# MyFly1.net
KiCad netlist of a schematic drawn in Altium Designer
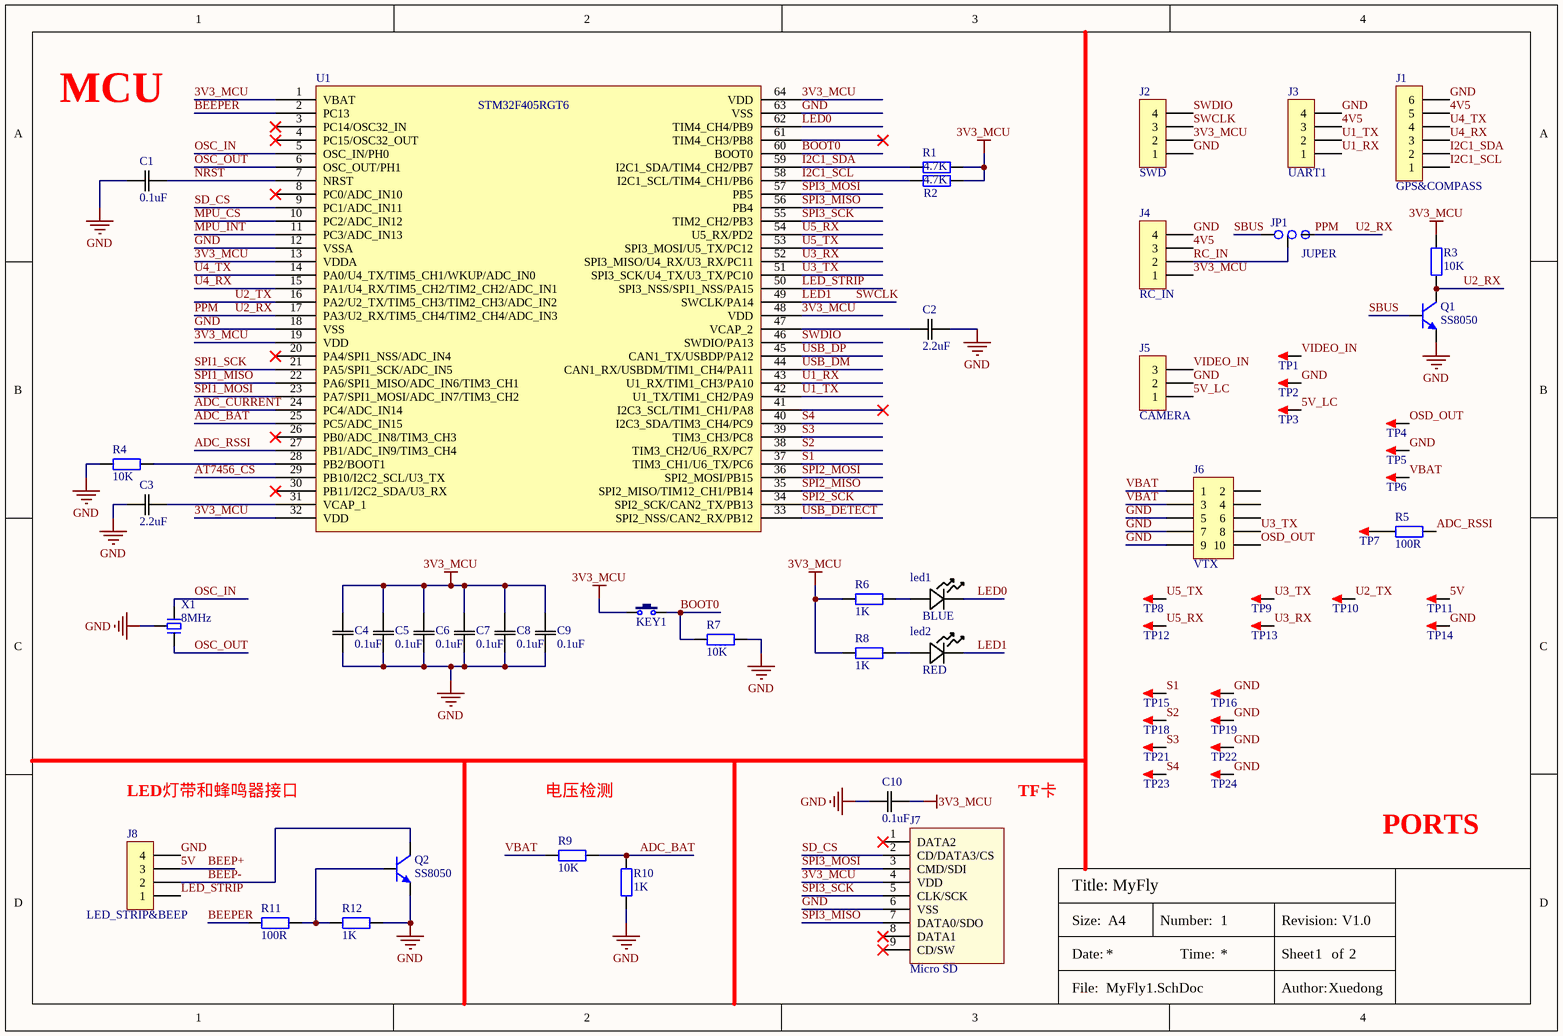
[diagram p0: MyFly1.SchDoc]

(export (version "E")
  (design (tool "Eeschema 10.0.6"))
  (components
    (comp (ref "C1")
      (value "0.1uF")
      (footprint "CAP_0402")
      (description "无极性贴片电容")
      (fields
        (field (name "MANUFACTURER_PART_NUMBER") "04023A0R3BAT2A")
        (field (name "COPYRIGHT") "Copyright (C) 2016 Accelerated Designs. All rights reserved")
      )
      (libsource (lib "mySchLib") (part "CAP"))
    )
    (comp (ref "C2")
      (value "2.2uF")
      (footprint "CAP_0402")
      (description "无极性贴片电容")
      (fields
        (field (name "MANUFACTURER_PART_NUMBER") "04023A0R3BAT2A")
        (field (name "COPYRIGHT") "Copyright (C) 2016 Accelerated Designs. All rights reserved")
      )
      (libsource (lib "mySchLib") (part "CAP"))
    )
    (comp (ref "C3")
      (value "2.2uF")
      (footprint "CAP_0402")
      (description "无极性贴片电容")
      (fields
        (field (name "MANUFACTURER_PART_NUMBER") "04023A0R3BAT2A")
        (field (name "COPYRIGHT") "Copyright (C) 2016 Accelerated Designs. All rights reserved")
      )
      (libsource (lib "mySchLib") (part "CAP"))
    )
    (comp (ref "C4")
      (value "0.1uF")
      (footprint "CAP_0402")
      (description "无极性贴片电容")
      (fields
        (field (name "MANUFACTURER_PART_NUMBER") "04023A0R3BAT2A")
        (field (name "COPYRIGHT") "Copyright (C) 2016 Accelerated Designs. All rights reserved")
      )
      (libsource (lib "mySchLib") (part "CAP"))
    )
    (comp (ref "C5")
      (value "0.1uF")
      (footprint "CAP_0402")
      (description "无极性贴片电容")
      (fields
        (field (name "MANUFACTURER_PART_NUMBER") "04023A0R3BAT2A")
        (field (name "COPYRIGHT") "Copyright (C) 2016 Accelerated Designs. All rights reserved")
      )
      (libsource (lib "mySchLib") (part "CAP"))
    )
    (comp (ref "C6")
      (value "0.1uF")
      (footprint "CAP_0402")
      (description "无极性贴片电容")
      (fields
        (field (name "MANUFACTURER_PART_NUMBER") "04023A0R3BAT2A")
        (field (name "COPYRIGHT") "Copyright (C) 2016 Accelerated Designs. All rights reserved")
      )
      (libsource (lib "mySchLib") (part "CAP"))
    )
    (comp (ref "C7")
      (value "0.1uF")
      (footprint "CAP_0402")
      (description "无极性贴片电容")
      (fields
        (field (name "MANUFACTURER_PART_NUMBER") "04023A0R3BAT2A")
        (field (name "COPYRIGHT") "Copyright (C) 2016 Accelerated Designs. All rights reserved")
      )
      (libsource (lib "mySchLib") (part "CAP"))
    )
    (comp (ref "C8")
      (value "0.1uF")
      (footprint "CAP_0402")
      (description "无极性贴片电容")
      (fields
        (field (name "MANUFACTURER_PART_NUMBER") "04023A0R3BAT2A")
        (field (name "COPYRIGHT") "Copyright (C) 2016 Accelerated Designs. All rights reserved")
      )
      (libsource (lib "mySchLib") (part "CAP"))
    )
    (comp (ref "C9")
      (value "0.1uF")
      (footprint "CAP_0402")
      (description "无极性贴片电容")
      (fields
        (field (name "MANUFACTURER_PART_NUMBER") "04023A0R3BAT2A")
        (field (name "COPYRIGHT") "Copyright (C) 2016 Accelerated Designs. All rights reserved")
      )
      (libsource (lib "mySchLib") (part "CAP"))
    )
    (comp (ref "C10")
      (value "0.1uF")
      (footprint "CAP_0603")
      (description "无极性贴片电容")
      (fields
        (field (name "MANUFACTURER_PART_NUMBER") "04023A0R3BAT2A")
        (field (name "COPYRIGHT") "Copyright (C) 2016 Accelerated Designs. All rights reserved")
      )
      (libsource (lib "mySchLib") (part "CAP"))
    )
    (comp (ref "J1")
      (value "GPS&COMPASS")
      (footprint "SH1.0 S-W-6P")
      (description "6P接插件")
      (fields (field (name "MANUFACTURER_PART_NUMBER") "826629-6"))
      (libsource (lib "mySchLib") (part "Header_1x6"))
    )
    (comp (ref "J2")
      (value "SWD")
      (footprint "SH1.0 S-W-4P")
      (description "4P接插件")
      (fields (field (name "MANUFACTURER_PART_NUMBER") "826629-4"))
      (libsource (lib "mySchLib") (part "Header_1x4"))
    )
    (comp (ref "J3")
      (value "UART1")
      (footprint "SH1.0 S-W-4P")
      (description "4P接插件")
      (fields (field (name "MANUFACTURER_PART_NUMBER") "826629-4"))
      (libsource (lib "mySchLib") (part "Header_1x4"))
    )
    (comp (ref "J4")
      (value "RC_IN")
      (footprint "SH1.0 S-W-4P")
      (description "4P接插件")
      (fields (field (name "MANUFACTURER_PART_NUMBER") "826629-4"))
      (libsource (lib "mySchLib") (part "Header_1x4"))
    )
    (comp (ref "J5")
      (value "CAMERA")
      (footprint "MX 1.25-WS-3P")
      (description "3P接插件")
      (fields (field (name "MANUFACTURER_PART_NUMBER") "826629-3"))
      (libsource (lib "mySchLib") (part "Header_1x3"))
    )
    (comp (ref "J6")
      (value "VTX")
      (footprint "HDR1.27 2x5-M-SMD")
      (description "2x5P-接插件")
      (fields (field (name "MANUFACTURER_PART_NUMBER") "826656-5"))
      (libsource (lib "mySchLib") (part "Header_2x5"))
    )
    (comp (ref "J7")
      (value "Micro SD")
      (footprint "MICRO SD")
      (description "Micro SD卡")
      (fields (field (name "版权归属") "源创客"))
      (libsource (lib "mySchLib") (part "Micro SD"))
    )
    (comp (ref "J8")
      (value "LED_STRIP&BEEP")
      (footprint "SH1.0 S-W-4P")
      (description "4P接插件")
      (fields (field (name "MANUFACTURER_PART_NUMBER") "826629-4"))
      (libsource (lib "mySchLib") (part "Header_1x4"))
    )
    (comp (ref "JP1")
      (value "JUPER")
      (footprint "JUMPER 3P")
      (description "三点焊盘跳线")
      (libsource (lib "mySchLib") (part "JUMPER 3P"))
    )
    (comp (ref "KEY1")
      (value "KEY")
      (footprint "KEY_TSW 2*4*3.5-S-W")
      (description "按键")
      (fields (field (name "版权归属") "源创客"))
      (libsource (lib "mySchLib") (part "KEY"))
    )
    (comp (ref "led1")
      (value "BLUE")
      (footprint "LED_0603")
      (description "贴片发光二极管")
      (fields (field (name "MANUFACTURER_PART_NUMBER") "VLMB1310-GS08"))
      (libsource (lib "mySchLib") (part "LED"))
    )
    (comp (ref "led2")
      (value "RED")
      (footprint "LED_0603")
      (description "贴片发光二极管")
      (fields (field (name "MANUFACTURER_PART_NUMBER") "VLMB1310-GS08"))
      (libsource (lib "mySchLib") (part "LED"))
    )
    (comp (ref "Q1")
      (value "SS8050")
      (footprint "SOT23-3L")
      (description "高频放大-NPN型")
      (fields (field (name "版权归属") "源创客"))
      (libsource (lib "mySchLib") (part "S8050-SMD"))
    )
    (comp (ref "Q2")
      (value "SS8050")
      (footprint "SOT23-3L")
      (description "高频放大-NPN型")
      (fields (field (name "版权归属") "源创客"))
      (libsource (lib "mySchLib") (part "S8050-SMD"))
    )
    (comp (ref "R1")
      (value "4.7K")
      (footprint "Res_0402")
      (description "贴片电阻")
      (fields (field (name "MANUFACTURER_PART_NUMBER") "RC0402FR-070RL"))
      (libsource (lib "mySchLib") (part "RES"))
    )
    (comp (ref "R2")
      (value "4.7K")
      (footprint "Res_0402")
      (description "贴片电阻")
      (fields (field (name "MANUFACTURER_PART_NUMBER") "RC0402FR-070RL"))
      (libsource (lib "mySchLib") (part "RES"))
    )
    (comp (ref "R3")
      (value "10K")
      (footprint "Res_0402")
      (description "贴片电阻")
      (fields (field (name "MANUFACTURER_PART_NUMBER") "RC0402FR-070RL"))
      (libsource (lib "mySchLib") (part "RES"))
    )
    (comp (ref "R4")
      (value "10K")
      (footprint "Res_0402")
      (description "贴片电阻")
      (fields (field (name "MANUFACTURER_PART_NUMBER") "RC0402FR-070RL"))
      (libsource (lib "mySchLib") (part "RES"))
    )
    (comp (ref "R5")
      (value "100R")
      (footprint "Res_0402")
      (description "贴片电阻")
      (fields (field (name "MANUFACTURER_PART_NUMBER") "RC0402FR-070RL"))
      (libsource (lib "mySchLib") (part "RES"))
    )
    (comp (ref "R6")
      (value "1K")
      (footprint "Res_0402")
      (description "贴片电阻")
      (fields (field (name "MANUFACTURER_PART_NUMBER") "RC0402FR-070RL"))
      (libsource (lib "mySchLib") (part "RES"))
    )
    (comp (ref "R7")
      (value "10K")
      (footprint "Res_0402")
      (description "贴片电阻")
      (fields (field (name "MANUFACTURER_PART_NUMBER") "RC0402FR-070RL"))
      (libsource (lib "mySchLib") (part "RES"))
    )
    (comp (ref "R8")
      (value "1K")
      (footprint "Res_0402")
      (description "贴片电阻")
      (fields (field (name "MANUFACTURER_PART_NUMBER") "RC0402FR-070RL"))
      (libsource (lib "mySchLib") (part "RES"))
    )
    (comp (ref "R9")
      (value "10K")
      (footprint "RES_0603")
      (description "贴片电阻")
      (fields (field (name "MANUFACTURER_PART_NUMBER") "RC0402FR-070RL"))
      (libsource (lib "mySchLib") (part "RES"))
    )
    (comp (ref "R10")
      (value "1K")
      (footprint "RES_0603")
      (description "贴片电阻")
      (fields (field (name "MANUFACTURER_PART_NUMBER") "RC0402FR-070RL"))
      (libsource (lib "mySchLib") (part "RES"))
    )
    (comp (ref "R11")
      (value "100R")
      (footprint "Res_0402")
      (description "贴片电阻")
      (fields (field (name "MANUFACTURER_PART_NUMBER") "RC0402FR-070RL"))
      (libsource (lib "mySchLib") (part "RES"))
    )
    (comp (ref "R12")
      (value "1K")
      (footprint "Res_0402")
      (description "贴片电阻")
      (fields (field (name "MANUFACTURER_PART_NUMBER") "RC0402FR-070RL"))
      (libsource (lib "mySchLib") (part "RES"))
    )
    (comp (ref "TP1")
      (value "TEST")
      (footprint "TEST PAD 1.8")
      (description "测试点")
      (fields (field (name "版权归属") "源创客"))
      (libsource (lib "mySchLib") (part "TEST"))
    )
    (comp (ref "TP2")
      (value "TEST")
      (footprint "TEST PAD 1.8")
      (description "测试点")
      (fields (field (name "版权归属") "源创客"))
      (libsource (lib "mySchLib") (part "TEST"))
    )
    (comp (ref "TP3")
      (value "TEST")
      (footprint "TEST PAD 1.8")
      (description "测试点")
      (fields (field (name "版权归属") "源创客"))
      (libsource (lib "mySchLib") (part "TEST"))
    )
    (comp (ref "TP4")
      (value "TEST")
      (footprint "TEST PAD 1.8")
      (description "测试点")
      (fields (field (name "版权归属") "源创客"))
      (libsource (lib "mySchLib") (part "TEST"))
    )
    (comp (ref "TP5")
      (value "TEST")
      (footprint "TEST PAD 1.8")
      (description "测试点")
      (fields (field (name "版权归属") "源创客"))
      (libsource (lib "mySchLib") (part "TEST"))
    )
    (comp (ref "TP6")
      (value "TEST")
      (footprint "TEST PAD 1.8")
      (description "测试点")
      (fields (field (name "版权归属") "源创客"))
      (libsource (lib "mySchLib") (part "TEST"))
    )
    (comp (ref "TP7")
      (value "TEST")
      (footprint "TEST PAD 1.8")
      (description "测试点")
      (fields (field (name "版权归属") "源创客"))
      (libsource (lib "mySchLib") (part "TEST"))
    )
    (comp (ref "TP8")
      (value "TEST")
      (footprint "TEST PAD 1.8")
      (description "测试点")
      (fields (field (name "版权归属") "源创客"))
      (libsource (lib "mySchLib") (part "TEST"))
    )
    (comp (ref "TP9")
      (value "TEST")
      (footprint "TEST PAD 1.8")
      (description "测试点")
      (fields (field (name "版权归属") "源创客"))
      (libsource (lib "mySchLib") (part "TEST"))
    )
    (comp (ref "TP10")
      (value "TEST")
      (footprint "TEST PAD 1.8")
      (description "测试点")
      (fields (field (name "版权归属") "源创客"))
      (libsource (lib "mySchLib") (part "TEST"))
    )
    (comp (ref "TP11")
      (value "TEST")
      (footprint "TEST PAD 1.8")
      (description "测试点")
      (fields (field (name "版权归属") "源创客"))
      (libsource (lib "mySchLib") (part "TEST"))
    )
    (comp (ref "TP12")
      (value "TEST")
      (footprint "TEST PAD 1.8")
      (description "测试点")
      (fields (field (name "版权归属") "源创客"))
      (libsource (lib "mySchLib") (part "TEST"))
    )
    (comp (ref "TP13")
      (value "TEST")
      (footprint "TEST PAD 1.8")
      (description "测试点")
      (fields (field (name "版权归属") "源创客"))
      (libsource (lib "mySchLib") (part "TEST"))
    )
    (comp (ref "TP14")
      (value "TEST")
      (footprint "TEST PAD 1.8")
      (description "测试点")
      (fields (field (name "版权归属") "源创客"))
      (libsource (lib "mySchLib") (part "TEST"))
    )
    (comp (ref "TP15")
      (value "TEST")
      (footprint "TEST PAD 1.8")
      (description "测试点")
      (fields (field (name "版权归属") "源创客"))
      (libsource (lib "mySchLib") (part "TEST"))
    )
    (comp (ref "TP16")
      (value "TEST")
      (footprint "TEST PAD 1.8")
      (description "测试点")
      (fields (field (name "版权归属") "源创客"))
      (libsource (lib "mySchLib") (part "TEST"))
    )
    (comp (ref "TP18")
      (value "TEST")
      (footprint "TEST PAD 1.8")
      (description "测试点")
      (fields (field (name "版权归属") "源创客"))
      (libsource (lib "mySchLib") (part "TEST"))
    )
    (comp (ref "TP19")
      (value "TEST")
      (footprint "TEST PAD 1.8")
      (description "测试点")
      (fields (field (name "版权归属") "源创客"))
      (libsource (lib "mySchLib") (part "TEST"))
    )
    (comp (ref "TP21")
      (value "TEST")
      (footprint "TEST PAD 1.8")
      (description "测试点")
      (fields (field (name "版权归属") "源创客"))
      (libsource (lib "mySchLib") (part "TEST"))
    )
    (comp (ref "TP22")
      (value "TEST")
      (footprint "TEST PAD 1.8")
      (description "测试点")
      (fields (field (name "版权归属") "源创客"))
      (libsource (lib "mySchLib") (part "TEST"))
    )
    (comp (ref "TP23")
      (value "TEST")
      (footprint "TEST PAD 1.8")
      (description "测试点")
      (fields (field (name "版权归属") "源创客"))
      (libsource (lib "mySchLib") (part "TEST"))
    )
    (comp (ref "TP24")
      (value "TEST")
      (footprint "TEST PAD 1.8")
      (description "测试点")
      (fields (field (name "版权归属") "源创客"))
      (libsource (lib "mySchLib") (part "TEST"))
    )
    (comp (ref "U1")
      (value "STM32F405RGT6")
      (footprint "LQFP-64")
      (description "Flaah:256/RAM:48/IO:51")
      (libsource (lib "mySchLib") (part "STM32F405RGT6"))
    )
    (comp (ref "X1")
      (value "8MHz")
      (footprint "XTAL-3215-3P")
      (description "3脚无源晶振")
      (fields (field (name "版权归属") "源创客"))
      (libsource (lib "mySchLib") (part "XTAL-3P"))
    )
  )
  (nets
    (net (code "1") (name "/4V5") (class "Default")
      (node (ref "J1") (pin "5") (pinfunction "5_5") (pintype "passive"))
      (node (ref "J3") (pin "3") (pinfunction "3_3") (pintype "passive"))
      (node (ref "J4") (pin "3") (pinfunction "3_3") (pintype "passive"))
    )
    (net (code "2") (name "/5V") (class "Default")
      (node (ref "J8") (pin "3") (pinfunction "3_3") (pintype "passive"))
      (node (ref "TP11") (pin "1") (pinfunction "1_1") (pintype "passive"))
    )
    (net (code "3") (name "/5V_LC") (class "Default")
      (node (ref "J5") (pin "1") (pinfunction "1_1") (pintype "passive"))
      (node (ref "TP3") (pin "1") (pinfunction "1_1") (pintype "passive"))
    )
    (net (code "4") (name "/ADC_BAT") (class "Default")
      (node (ref "R10") (pin "2") (pinfunction "2_2") (pintype "passive"))
      (node (ref "R9") (pin "2") (pinfunction "2_2") (pintype "passive"))
      (node (ref "U1") (pin "25") (pinfunction "PC5/ADC_IN15_25") (pintype "passive"))
    )
    (net (code "5") (name "/ADC_CURRENT") (class "Default")
      (node (ref "U1") (pin "24") (pinfunction "PC4/ADC_IN14_24") (pintype "passive"))
    )
    (net (code "6") (name "/ADC_RSSI") (class "Default")
      (node (ref "R5") (pin "2") (pinfunction "2_2") (pintype "passive"))
      (node (ref "U1") (pin "27") (pinfunction "PB1/ADC_IN9/TIM3_CH4_27") (pintype "passive"))
    )
    (net (code "7") (name "/AT7456_CS") (class "Default")
      (node (ref "U1") (pin "29") (pinfunction "PB10/I2C2_SCL/U3_TX_29") (pintype "passive"))
    )
    (net (code "8") (name "/BEEP-") (class "Default")
      (node (ref "J8") (pin "2") (pinfunction "2_2") (pintype "passive"))
      (node (ref "Q2") (pin "3") (pinfunction "C_3") (pintype "passive"))
    )
    (net (code "9") (name "/BEEPER") (class "Default")
      (node (ref "R11") (pin "1") (pinfunction "1_1") (pintype "passive"))
      (node (ref "U1") (pin "2") (pinfunction "PC13_2") (pintype "passive"))
    )
    (net (code "10") (name "/BOOT0") (class "Default")
      (node (ref "KEY1") (pin "2") (pinfunction "2_2") (pintype "passive"))
      (node (ref "R7") (pin "1") (pinfunction "1_1") (pintype "passive"))
      (node (ref "U1") (pin "60") (pinfunction "BOOT0_60") (pintype "passive"))
    )
    (net (code "11") (name "/I2C1_SCL") (class "Default")
      (node (ref "J1") (pin "1") (pinfunction "1_1") (pintype "passive"))
      (node (ref "R2") (pin "1") (pinfunction "1_1") (pintype "passive"))
      (node (ref "U1") (pin "58") (pinfunction "I2C1_SCL/TIM4_CH1/PB6_58") (pintype "passive"))
    )
    (net (code "12") (name "/I2C1_SDA") (class "Default")
      (node (ref "J1") (pin "2") (pinfunction "2_2") (pintype "passive"))
      (node (ref "R1") (pin "1") (pinfunction "1_1") (pintype "passive"))
      (node (ref "U1") (pin "59") (pinfunction "I2C1_SDA/TIM4_CH2/PB7_59") (pintype "passive"))
    )
    (net (code "13") (name "/LED0") (class "Default")
      (node (ref "U1") (pin "62") (pinfunction "TIM4_CH4/PB9_62") (pintype "passive"))
      (node (ref "led1") (pin "1") (pinfunction "1_1") (pintype "passive"))
    )
    (net (code "14") (name "/LED1") (class "Default")
      (node (ref "J2") (pin "3") (pinfunction "3_3") (pintype "passive"))
      (node (ref "U1") (pin "49") (pinfunction "SWCLK/PA14_49") (pintype "passive"))
      (node (ref "led2") (pin "1") (pinfunction "1_1") (pintype "passive"))
    )
    (net (code "15") (name "/LED_STRIP") (class "Default")
      (node (ref "J8") (pin "1") (pinfunction "1_1") (pintype "passive"))
      (node (ref "U1") (pin "50") (pinfunction "SPI3_NSS/SPI1_NSS/PA15_50") (pintype "passive"))
    )
    (net (code "16") (name "/MPU_CS") (class "Default")
      (node (ref "U1") (pin "10") (pinfunction "PC2/ADC_IN12_10") (pintype "passive"))
    )
    (net (code "17") (name "/MPU_INT") (class "Default")
      (node (ref "U1") (pin "11") (pinfunction "PC3/ADC_IN13_11") (pintype "passive"))
    )
    (net (code "18") (name "/NRST") (class "Default")
      (node (ref "C1") (pin "2") (pinfunction "EPAD_2") (pintype "passive"))
      (node (ref "U1") (pin "7") (pinfunction "NRST_7") (pintype "passive"))
    )
    (net (code "19") (name "/OSC_IN") (class "Default")
      (node (ref "U1") (pin "5") (pinfunction "OSC_IN/PH0_5") (pintype "passive"))
      (node (ref "X1") (pin "1") (pinfunction "1_1") (pintype "passive"))
    )
    (net (code "20") (name "/OSC_OUT") (class "Default")
      (node (ref "U1") (pin "6") (pinfunction "OSC_OUT/PH1_6") (pintype "passive"))
      (node (ref "X1") (pin "3") (pinfunction "3_3") (pintype "passive"))
    )
    (net (code "21") (name "/OSD_OUT") (class "Default")
      (node (ref "J6") (pin "10") (pinfunction "10_10") (pintype "passive"))
      (node (ref "TP4") (pin "1") (pinfunction "1_1") (pintype "passive"))
    )
    (net (code "22") (name "/PPM") (class "Default")
      (node (ref "JP1") (pin "3") (pinfunction "3_3") (pintype "passive"))
      (node (ref "Q1") (pin "3") (pinfunction "C_3") (pintype "passive"))
      (node (ref "R3") (pin "1") (pinfunction "1_1") (pintype "passive"))
      (node (ref "U1") (pin "17") (pinfunction "PA3/U2_RX/TIM5_CH4/TIM2_CH4/ADC_IN3_17") (pintype "passive"))
    )
    (net (code "23") (name "/RC_IN") (class "Default")
      (node (ref "J4") (pin "2") (pinfunction "2_2") (pintype "passive"))
      (node (ref "JP1") (pin "2") (pinfunction "2_2") (pintype "passive"))
    )
    (net (code "24") (name "/S1") (class "Default")
      (node (ref "TP15") (pin "1") (pinfunction "1_1") (pintype "passive"))
      (node (ref "U1") (pin "37") (pinfunction "TIM3_CH1/U6_TX/PC6_37") (pintype "passive"))
    )
    (net (code "25") (name "/S2") (class "Default")
      (node (ref "TP18") (pin "1") (pinfunction "1_1") (pintype "passive"))
      (node (ref "U1") (pin "38") (pinfunction "TIM3_CH2/U6_RX/PC7_38") (pintype "passive"))
    )
    (net (code "26") (name "/S3") (class "Default")
      (node (ref "TP21") (pin "1") (pinfunction "1_1") (pintype "passive"))
      (node (ref "U1") (pin "39") (pinfunction "TIM3_CH3/PC8_39") (pintype "passive"))
    )
    (net (code "27") (name "/S4") (class "Default")
      (node (ref "TP23") (pin "1") (pinfunction "1_1") (pintype "passive"))
      (node (ref "U1") (pin "40") (pinfunction "I2C3_SDA/TIM3_CH4/PC9_40") (pintype "passive"))
    )
    (net (code "28") (name "/SBUS") (class "Default")
      (node (ref "JP1") (pin "1") (pinfunction "1_1") (pintype "passive"))
      (node (ref "Q1") (pin "1") (pinfunction "B_1") (pintype "passive"))
    )
    (net (code "29") (name "/SD_CS") (class "Default")
      (node (ref "J7") (pin "2") (pinfunction "CD/DATA3/CS_2") (pintype "passive"))
      (node (ref "U1") (pin "9") (pinfunction "PC1/ADC_IN11_9") (pintype "passive"))
    )
    (net (code "30") (name "/SPI1_MISO") (class "Default")
      (node (ref "U1") (pin "22") (pinfunction "PA6/SPI1_MISO/ADC_IN6/TIM3_CH1_22") (pintype "passive"))
    )
    (net (code "31") (name "/SPI1_MOSI") (class "Default")
      (node (ref "U1") (pin "23") (pinfunction "PA7/SPI1_MOSI/ADC_IN7/TIM3_CH2_23") (pintype "passive"))
    )
    (net (code "32") (name "/SPI1_SCK") (class "Default")
      (node (ref "U1") (pin "21") (pinfunction "PA5/SPI1_SCK/ADC_IN5_21") (pintype "passive"))
    )
    (net (code "33") (name "/SPI2_MISO") (class "Default")
      (node (ref "U1") (pin "35") (pinfunction "SPI2_MISO/TIM12_CH1/PB14_35") (pintype "passive"))
    )
    (net (code "34") (name "/SPI2_MOSI") (class "Default")
      (node (ref "U1") (pin "36") (pinfunction "SPI2_MOSI/PB15_36") (pintype "passive"))
    )
    (net (code "35") (name "/SPI2_SCK") (class "Default")
      (node (ref "U1") (pin "34") (pinfunction "SPI2_SCK/CAN2_TX/PB13_34") (pintype "passive"))
    )
    (net (code "36") (name "/SPI3_MISO") (class "Default")
      (node (ref "J7") (pin "7") (pinfunction "DATA0/SDO_7") (pintype "passive"))
      (node (ref "U1") (pin "56") (pinfunction "PB4_56") (pintype "passive"))
    )
    (net (code "37") (name "/SPI3_MOSI") (class "Default")
      (node (ref "J7") (pin "3") (pinfunction "CMD/SDI_3") (pintype "passive"))
      (node (ref "U1") (pin "57") (pinfunction "PB5_57") (pintype "passive"))
    )
    (net (code "38") (name "/SPI3_SCK") (class "Default")
      (node (ref "J7") (pin "5") (pinfunction "CLK/SCK_5") (pintype "passive"))
      (node (ref "U1") (pin "55") (pinfunction "TIM2_CH2/PB3_55") (pintype "passive"))
    )
    (net (code "39") (name "/SWDIO") (class "Default")
      (node (ref "J2") (pin "4") (pinfunction "4_4") (pintype "passive"))
      (node (ref "U1") (pin "46") (pinfunction "SWDIO/PA13_46") (pintype "passive"))
    )
    (net (code "40") (name "/U1_RX") (class "Default")
      (node (ref "J3") (pin "1") (pinfunction "1_1") (pintype "passive"))
      (node (ref "U1") (pin "43") (pinfunction "U1_RX/TIM1_CH3/PA10_43") (pintype "passive"))
    )
    (net (code "41") (name "/U1_TX") (class "Default")
      (node (ref "J3") (pin "2") (pinfunction "2_2") (pintype "passive"))
      (node (ref "U1") (pin "42") (pinfunction "U1_TX/TIM1_CH2/PA9_42") (pintype "passive"))
    )
    (net (code "42") (name "/U2_TX") (class "Default")
      (node (ref "TP10") (pin "1") (pinfunction "1_1") (pintype "passive"))
      (node (ref "U1") (pin "16") (pinfunction "PA2/U2_TX/TIM5_CH3/TIM2_CH3/ADC_IN2_16") (pintype "passive"))
    )
    (net (code "43") (name "/U3_RX") (class "Default")
      (node (ref "TP13") (pin "1") (pinfunction "1_1") (pintype "passive"))
      (node (ref "U1") (pin "52") (pinfunction "SPI3_MISO/U4_RX/U3_RX/PC11_52") (pintype "passive"))
    )
    (net (code "44") (name "/U3_TX") (class "Default")
      (node (ref "J6") (pin "8") (pinfunction "8_8") (pintype "passive"))
      (node (ref "TP9") (pin "1") (pinfunction "1_1") (pintype "passive"))
      (node (ref "U1") (pin "51") (pinfunction "SPI3_SCK/U4_TX/U3_TX/PC10_51") (pintype "passive"))
    )
    (net (code "45") (name "/U4_RX") (class "Default")
      (node (ref "J1") (pin "3") (pinfunction "3_3") (pintype "passive"))
      (node (ref "U1") (pin "15") (pinfunction "PA1/U4_RX/TIM5_CH2/TIM2_CH2/ADC_IN1_15") (pintype "passive"))
    )
    (net (code "46") (name "/U4_TX") (class "Default")
      (node (ref "J1") (pin "4") (pinfunction "4_4") (pintype "passive"))
      (node (ref "U1") (pin "14") (pinfunction "PA0/U4_TX/TIM5_CH1/WKUP/ADC_IN0_14") (pintype "passive"))
    )
    (net (code "47") (name "/U5_RX") (class "Default")
      (node (ref "TP12") (pin "1") (pinfunction "1_1") (pintype "passive"))
      (node (ref "U1") (pin "54") (pinfunction "U5_RX/PD2_54") (pintype "passive"))
    )
    (net (code "48") (name "/U5_TX") (class "Default")
      (node (ref "TP8") (pin "1") (pinfunction "1_1") (pintype "passive"))
      (node (ref "U1") (pin "53") (pinfunction "SPI3_MOSI/U5_TX/PC12_53") (pintype "passive"))
    )
    (net (code "49") (name "/USB_DETECT") (class "Default")
      (node (ref "U1") (pin "33") (pinfunction "SPI2_NSS/CAN2_RX/PB12_33") (pintype "passive"))
    )
    (net (code "50") (name "/USB_DM") (class "Default")
      (node (ref "U1") (pin "44") (pinfunction "CAN1_RX/USBDM/TIM1_CH4/PA11_44") (pintype "passive"))
    )
    (net (code "51") (name "/USB_DP") (class "Default")
      (node (ref "U1") (pin "45") (pinfunction "CAN1_TX/USBDP/PA12_45") (pintype "passive"))
    )
    (net (code "52") (name "/VBAT") (class "Default")
      (node (ref "J6") (pin "1") (pinfunction "1_1") (pintype "passive"))
      (node (ref "J6") (pin "3") (pinfunction "3_3") (pintype "passive"))
      (node (ref "R9") (pin "1") (pinfunction "1_1") (pintype "passive"))
      (node (ref "TP6") (pin "1") (pinfunction "1_1") (pintype "passive"))
    )
    (net (code "53") (name "/VIDEO_IN") (class "Default")
      (node (ref "J5") (pin "3") (pinfunction "3_3") (pintype "passive"))
      (node (ref "TP1") (pin "1") (pinfunction "1_1") (pintype "passive"))
    )
    (net (code "54") (name "3V3_MCU") (class "Default")
      (node (ref "C10") (pin "2") (pinfunction "EPAD_2") (pintype "passive"))
      (node (ref "C4") (pin "2") (pinfunction "EPAD_2") (pintype "passive"))
      (node (ref "C5") (pin "2") (pinfunction "EPAD_2") (pintype "passive"))
      (node (ref "C6") (pin "2") (pinfunction "EPAD_2") (pintype "passive"))
      (node (ref "C7") (pin "2") (pinfunction "EPAD_2") (pintype "passive"))
      (node (ref "C8") (pin "2") (pinfunction "EPAD_2") (pintype "passive"))
      (node (ref "C9") (pin "2") (pinfunction "EPAD_2") (pintype "passive"))
      (node (ref "J2") (pin "2") (pinfunction "2_2") (pintype "passive"))
      (node (ref "J4") (pin "1") (pinfunction "1_1") (pintype "passive"))
      (node (ref "J7") (pin "4") (pinfunction "VDD_4") (pintype "passive"))
      (node (ref "KEY1") (pin "1") (pinfunction "1_1") (pintype "passive"))
      (node (ref "R1") (pin "2") (pinfunction "2_2") (pintype "passive"))
      (node (ref "R2") (pin "2") (pinfunction "2_2") (pintype "passive"))
      (node (ref "R3") (pin "2") (pinfunction "2_2") (pintype "passive"))
      (node (ref "R6") (pin "1") (pinfunction "1_1") (pintype "passive"))
      (node (ref "R8") (pin "1") (pinfunction "1_1") (pintype "passive"))
      (node (ref "U1") (pin "1") (pinfunction "VBAT_1") (pintype "passive"))
      (node (ref "U1") (pin "13") (pinfunction "VDDA_13") (pintype "passive"))
      (node (ref "U1") (pin "19") (pinfunction "VDD_19") (pintype "passive"))
      (node (ref "U1") (pin "32") (pinfunction "VDD_32") (pintype "passive"))
      (node (ref "U1") (pin "48") (pinfunction "VDD_48") (pintype "passive"))
      (node (ref "U1") (pin "64") (pinfunction "VDD_64") (pintype "passive"))
    )
    (net (code "55") (name "GND") (class "Default")
      (node (ref "C1") (pin "1") (pinfunction "EPAD_1") (pintype "passive"))
      (node (ref "C10") (pin "1") (pinfunction "EPAD_1") (pintype "passive"))
      (node (ref "C2") (pin "2") (pinfunction "EPAD_2") (pintype "passive"))
      (node (ref "C3") (pin "1") (pinfunction "EPAD_1") (pintype "passive"))
      (node (ref "C4") (pin "1") (pinfunction "EPAD_1") (pintype "passive"))
      (node (ref "C5") (pin "1") (pinfunction "EPAD_1") (pintype "passive"))
      (node (ref "C6") (pin "1") (pinfunction "EPAD_1") (pintype "passive"))
      (node (ref "C7") (pin "1") (pinfunction "EPAD_1") (pintype "passive"))
      (node (ref "C8") (pin "1") (pinfunction "EPAD_1") (pintype "passive"))
      (node (ref "C9") (pin "1") (pinfunction "EPAD_1") (pintype "passive"))
      (node (ref "J1") (pin "6") (pinfunction "6_6") (pintype "passive"))
      (node (ref "J2") (pin "1") (pinfunction "1_1") (pintype "passive"))
      (node (ref "J3") (pin "4") (pinfunction "4_4") (pintype "passive"))
      (node (ref "J4") (pin "4") (pinfunction "4_4") (pintype "passive"))
      (node (ref "J5") (pin "2") (pinfunction "2_2") (pintype "passive"))
      (node (ref "J6") (pin "5") (pinfunction "5_5") (pintype "passive"))
      (node (ref "J6") (pin "7") (pinfunction "7_7") (pintype "passive"))
      (node (ref "J6") (pin "9") (pinfunction "9_9") (pintype "passive"))
      (node (ref "J7") (pin "6") (pinfunction "VSS_6") (pintype "passive"))
      (node (ref "J8") (pin "4") (pinfunction "4_4") (pintype "passive"))
      (node (ref "Q1") (pin "2") (pinfunction "E_2") (pintype "passive"))
      (node (ref "Q2") (pin "2") (pinfunction "E_2") (pintype "passive"))
      (node (ref "R10") (pin "1") (pinfunction "1_1") (pintype "passive"))
      (node (ref "R12") (pin "2") (pinfunction "2_2") (pintype "passive"))
      (node (ref "R4") (pin "1") (pinfunction "1_1") (pintype "passive"))
      (node (ref "R7") (pin "2") (pinfunction "2_2") (pintype "passive"))
      (node (ref "TP14") (pin "1") (pinfunction "1_1") (pintype "passive"))
      (node (ref "TP16") (pin "1") (pinfunction "1_1") (pintype "passive"))
      (node (ref "TP19") (pin "1") (pinfunction "1_1") (pintype "passive"))
      (node (ref "TP2") (pin "1") (pinfunction "1_1") (pintype "passive"))
      (node (ref "TP22") (pin "1") (pinfunction "1_1") (pintype "passive"))
      (node (ref "TP24") (pin "1") (pinfunction "1_1") (pintype "passive"))
      (node (ref "TP5") (pin "1") (pinfunction "1_1") (pintype "passive"))
      (node (ref "U1") (pin "12") (pinfunction "VSSA_12") (pintype "passive"))
      (node (ref "U1") (pin "18") (pinfunction "VSS_18") (pintype "passive"))
      (node (ref "U1") (pin "63") (pinfunction "VSS_63") (pintype "passive"))
      (node (ref "X1") (pin "2") (pinfunction "2_2") (pintype "passive"))
    )
    (net (code "56") (name "Net-(Q2-B)") (class "Default")
      (node (ref "Q2") (pin "1") (pinfunction "B_1") (pintype "passive"))
      (node (ref "R11") (pin "2") (pinfunction "2_2") (pintype "passive"))
      (node (ref "R12") (pin "1") (pinfunction "1_1") (pintype "passive"))
    )
    (net (code "57") (name "Net-(R5-Pad1)") (class "Default")
      (node (ref "R5") (pin "1") (pinfunction "1_1") (pintype "passive"))
      (node (ref "TP7") (pin "1") (pinfunction "1_1") (pintype "passive"))
    )
    (net (code "58") (name "Net-(R6-Pad2)") (class "Default")
      (node (ref "R6") (pin "2") (pinfunction "2_2") (pintype "passive"))
      (node (ref "led1") (pin "2") (pinfunction "2_2") (pintype "passive"))
    )
    (net (code "59") (name "Net-(R8-Pad2)") (class "Default")
      (node (ref "R8") (pin "2") (pinfunction "2_2") (pintype "passive"))
      (node (ref "led2") (pin "2") (pinfunction "2_2") (pintype "passive"))
    )
    (net (code "60") (name "Net-(U1-PB2{slash}BOOT1)") (class "Default")
      (node (ref "R4") (pin "2") (pinfunction "2_2") (pintype "passive"))
      (node (ref "U1") (pin "28") (pinfunction "PB2/BOOT1_28") (pintype "passive"))
    )
    (net (code "61") (name "Net-(U1-VCAP_1)") (class "Default")
      (node (ref "C3") (pin "2") (pinfunction "EPAD_2") (pintype "passive"))
      (node (ref "U1") (pin "31") (pinfunction "VCAP_1_31") (pintype "passive"))
    )
    (net (code "62") (name "Net-(U1-VCAP_2)") (class "Default")
      (node (ref "C2") (pin "1") (pinfunction "EPAD_1") (pintype "passive"))
      (node (ref "U1") (pin "47") (pinfunction "VCAP_2_47") (pintype "passive"))
    )
    (net (code "63") (name "unconnected-(J6-Pad2)") (class "Default")
      (node (ref "J6") (pin "2") (pinfunction "2_2") (pintype "passive"))
    )
    (net (code "64") (name "unconnected-(J6-Pad4)") (class "Default")
      (node (ref "J6") (pin "4") (pinfunction "4_4") (pintype "passive"))
    )
    (net (code "65") (name "unconnected-(J6-Pad6)") (class "Default")
      (node (ref "J6") (pin "6") (pinfunction "6_6") (pintype "passive"))
    )
    (net (code "66") (name "unconnected-(J7-CD{slash}SW-Pad9)") (class "Default")
      (node (ref "J7") (pin "9") (pinfunction "CD/SW_9") (pintype "passive+no_connect"))
    )
    (net (code "67") (name "unconnected-(J7-DATA1-Pad8)") (class "Default")
      (node (ref "J7") (pin "8") (pinfunction "DATA1_8") (pintype "passive+no_connect"))
    )
    (net (code "68") (name "unconnected-(J7-DATA2-Pad1)") (class "Default")
      (node (ref "J7") (pin "1") (pinfunction "DATA2_1") (pintype "passive+no_connect"))
    )
    (net (code "69") (name "unconnected-(U1-I2C3_SCL{slash}TIM1_CH1{slash}PA8-Pad41)") (class "Default")
      (node (ref "U1") (pin "41") (pinfunction "I2C3_SCL/TIM1_CH1/PA8_41") (pintype "passive+no_connect"))
    )
    (net (code "70") (name "unconnected-(U1-PA4{slash}SPI1_NSS{slash}ADC_IN4-Pad20)") (class "Default")
      (node (ref "U1") (pin "20") (pinfunction "PA4/SPI1_NSS/ADC_IN4_20") (pintype "passive+no_connect"))
    )
    (net (code "71") (name "unconnected-(U1-PB0{slash}ADC_IN8{slash}TIM3_CH3-Pad26)") (class "Default")
      (node (ref "U1") (pin "26") (pinfunction "PB0/ADC_IN8/TIM3_CH3_26") (pintype "passive+no_connect"))
    )
    (net (code "72") (name "unconnected-(U1-PB11{slash}I2C2_SDA{slash}U3_RX-Pad30)") (class "Default")
      (node (ref "U1") (pin "30") (pinfunction "PB11/I2C2_SDA/U3_RX_30") (pintype "passive+no_connect"))
    )
    (net (code "73") (name "unconnected-(U1-PC0{slash}ADC_IN10-Pad8)") (class "Default")
      (node (ref "U1") (pin "8") (pinfunction "PC0/ADC_IN10_8") (pintype "passive+no_connect"))
    )
    (net (code "74") (name "unconnected-(U1-PC14{slash}OSC32_IN-Pad3)") (class "Default")
      (node (ref "U1") (pin "3") (pinfunction "PC14/OSC32_IN_3") (pintype "passive+no_connect"))
    )
    (net (code "75") (name "unconnected-(U1-PC15{slash}OSC32_OUT-Pad4)") (class "Default")
      (node (ref "U1") (pin "4") (pinfunction "PC15/OSC32_OUT_4") (pintype "passive+no_connect"))
    )
    (net (code "76") (name "unconnected-(U1-TIM4_CH3{slash}PB8-Pad61)") (class "Default")
      (node (ref "U1") (pin "61") (pinfunction "TIM4_CH3/PB8_61") (pintype "passive+no_connect"))
    )
  )
)
